# GBA.net
KiCad netlist of a schematic drawn in Altium Designer
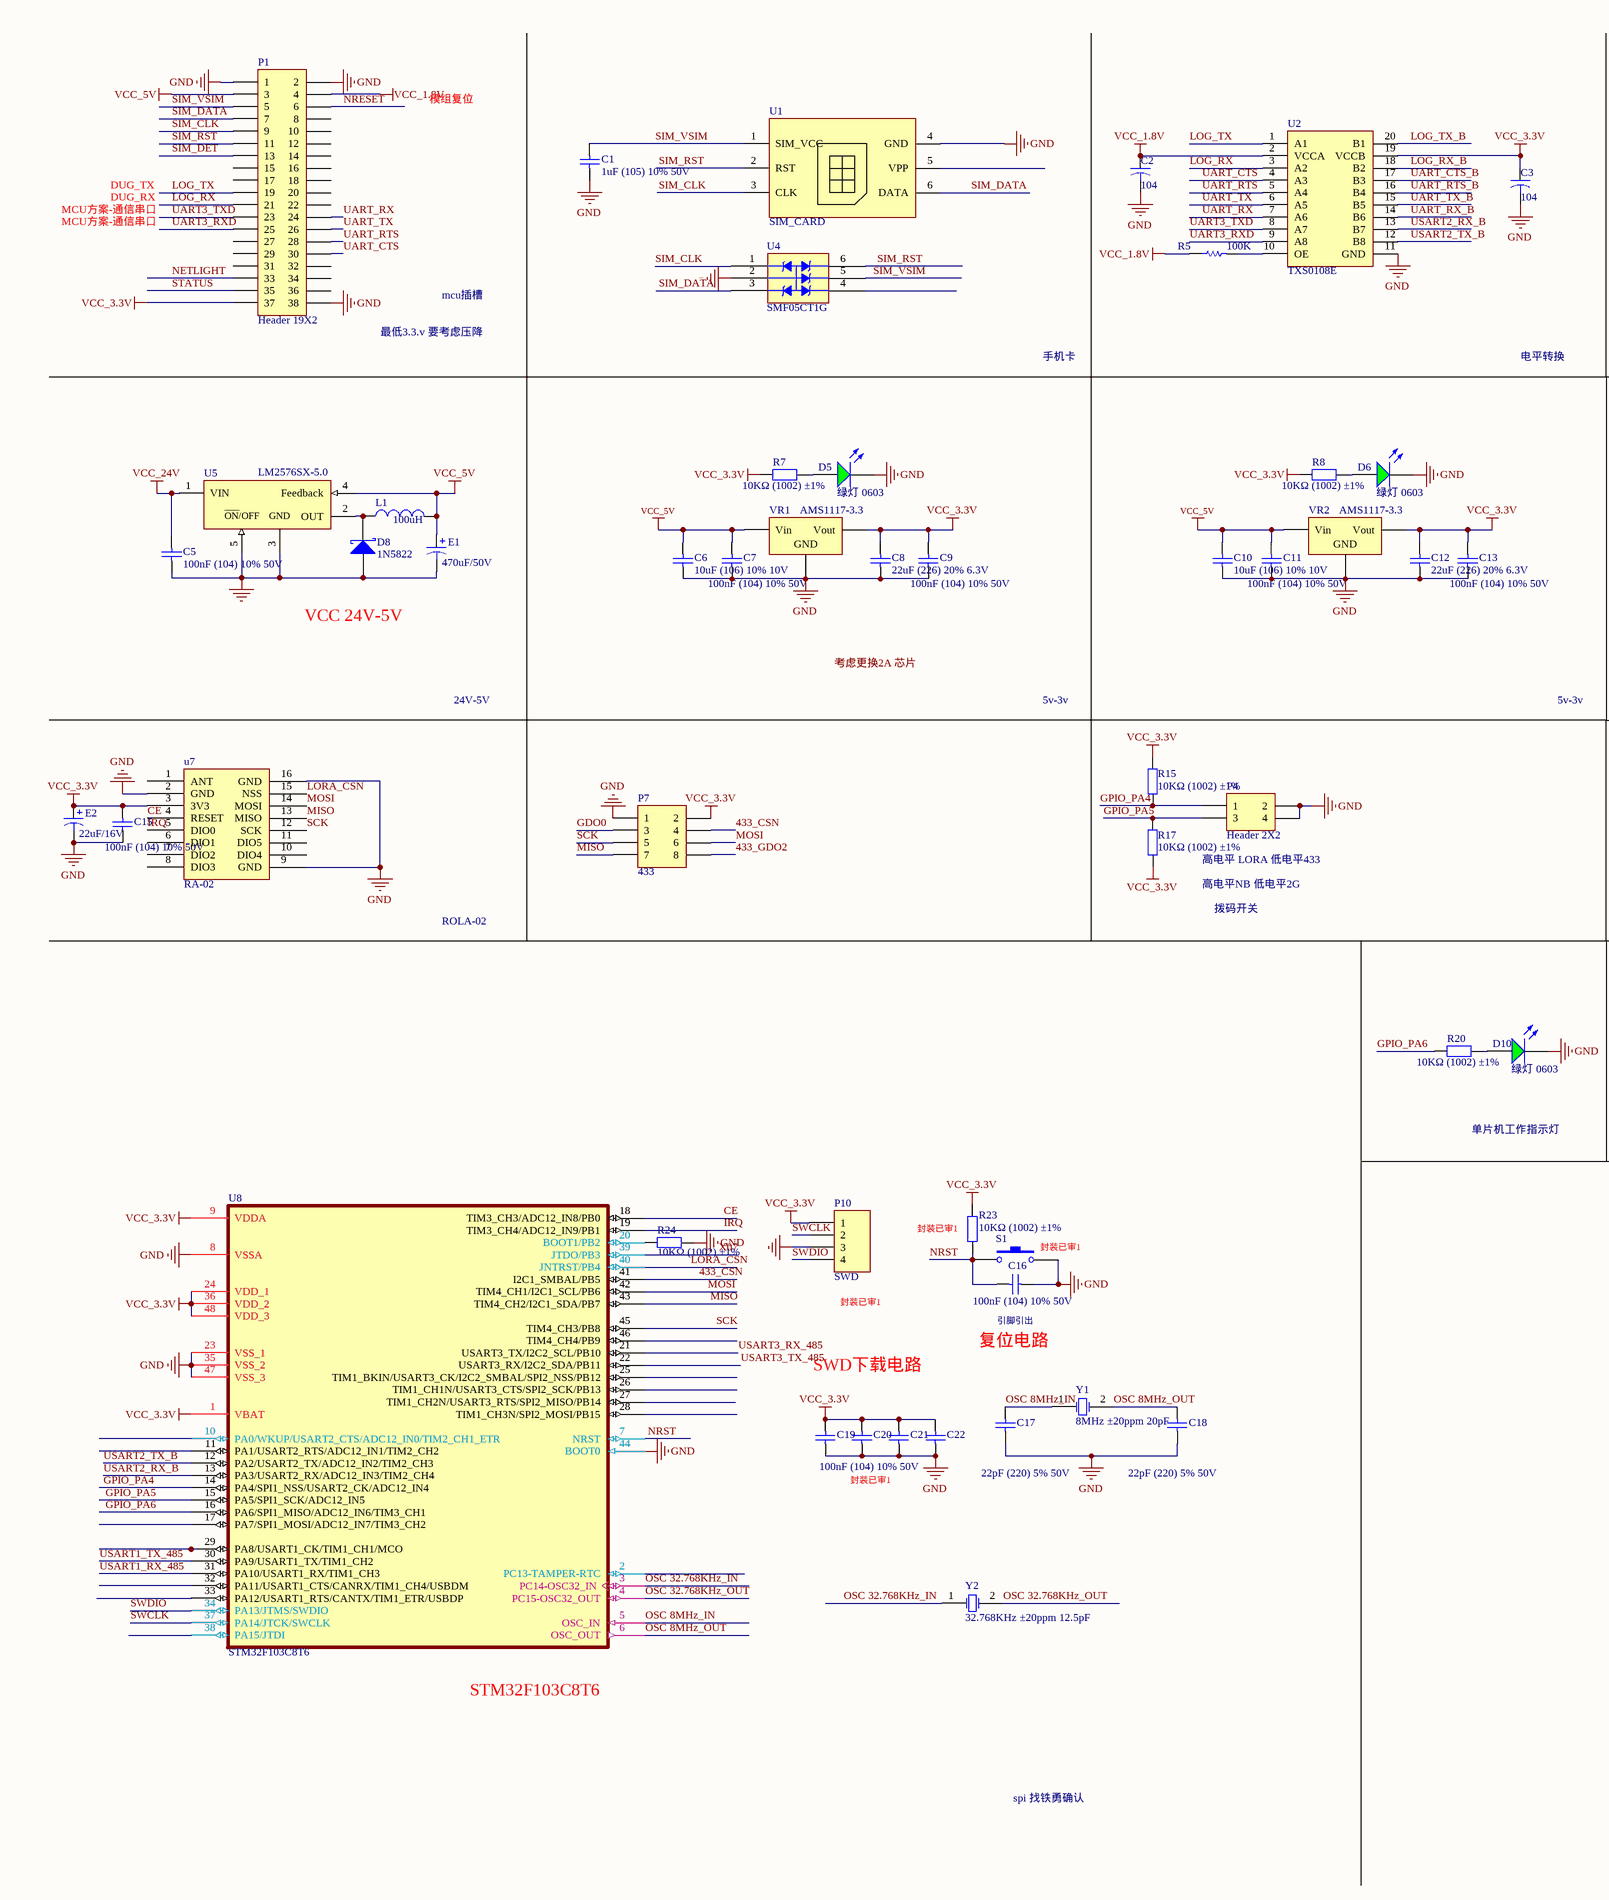
[diagram p0: GBA.SchDoc, left]
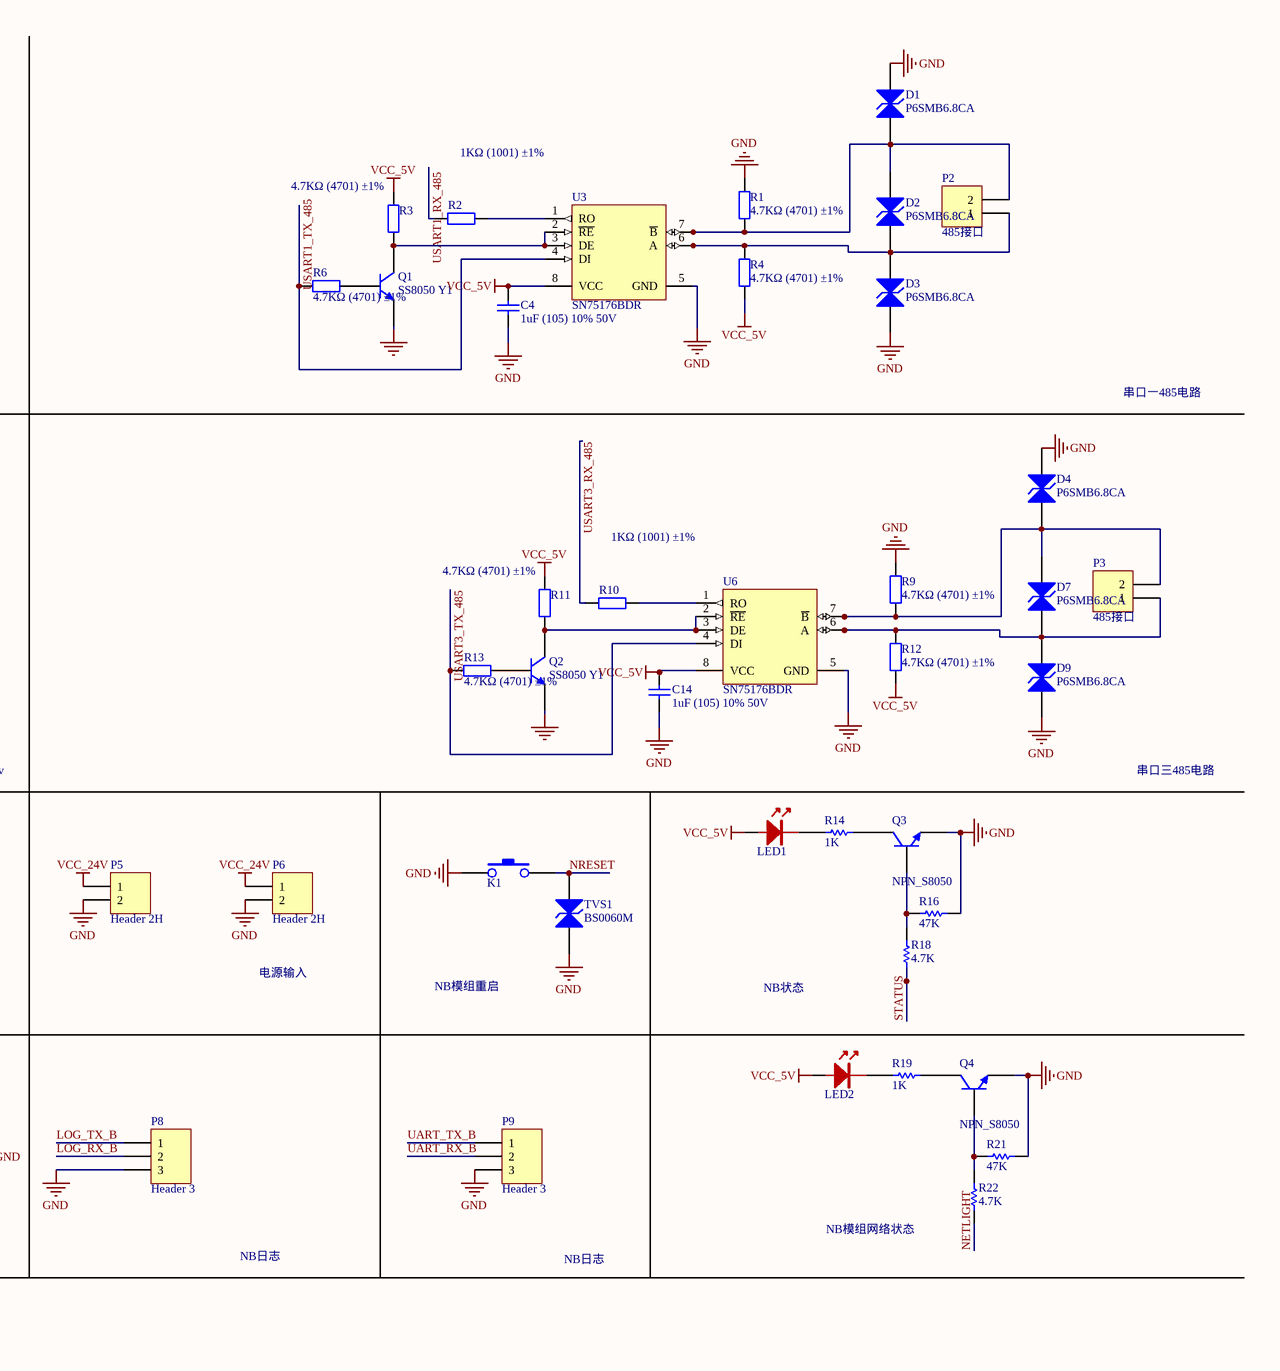
[diagram p1: GBA.SchDoc, right]

(export (version "E")
  (design (tool "Eeschema 10.0.6"))
  (components
    (comp (ref "C1")
      (value "1uF (105) 10% 50V")
      (footprint "0603_C")
      (description "贴片电容")
      (libsource (lib "Miscellaneous Devices LC (1)") (part "0603 1uF (105) 10% 50V"))
    )
    (comp (ref "C2") (value "104") (footprint "0603_s") (libsource (lib "WS_protel_lib") (part "Cap2")))
    (comp (ref "C3") (value "104") (footprint "0603_s") (libsource (lib "WS_protel_lib") (part "Cap2")))
    (comp (ref "C4")
      (value "1uF (105) 10% 50V")
      (footprint "0603_C")
      (description "贴片电容")
      (libsource (lib "Miscellaneous Devices LC (1)") (part "0603 1uF (105) 10% 50V"))
    )
    (comp (ref "C5")
      (value "100nF (104) 10% 50V")
      (footprint "0603_C")
      (description "贴片电容")
      (libsource (lib "Miscellaneous Devices LC") (part "0603 100nF (104) 10% 50V"))
    )
    (comp (ref "C6")
      (value "10uF (106) 10% 10V")
      (footprint "0603_C")
      (description "贴片电容")
      (libsource (lib "Miscellaneous Devices LC") (part "0603 10uF (106) 10% 10V"))
    )
    (comp (ref "C7")
      (value "100nF (104) 10% 50V")
      (footprint "CAPC_0603_2")
      (description "贴片电容")
      (libsource (lib "Cap") (part "0603 100nF (104) 10% 50V"))
    )
    (comp (ref "C8")
      (value "22uF (226) 20% 6.3V")
      (footprint "0603_C")
      (description "贴片电容")
      (libsource (lib "Miscellaneous Devices LC") (part "0603 22uF (226) 20% 6.3V"))
    )
    (comp (ref "C9")
      (value "100nF (104) 10% 50V")
      (footprint "CAPC_0603_2")
      (description "贴片电容")
      (libsource (lib "Cap") (part "0603 100nF (104) 10% 50V"))
    )
    (comp (ref "C10")
      (value "10uF (106) 10% 10V")
      (footprint "0603_C")
      (description "贴片电容")
      (libsource (lib "Miscellaneous Devices LC") (part "0603 10uF (106) 10% 10V"))
    )
    (comp (ref "C11")
      (value "100nF (104) 10% 50V")
      (footprint "CAPC_0603_2")
      (description "贴片电容")
      (libsource (lib "Cap") (part "0603 100nF (104) 10% 50V"))
    )
    (comp (ref "C12")
      (value "22uF (226) 20% 6.3V")
      (footprint "0603_C")
      (description "贴片电容")
      (libsource (lib "Miscellaneous Devices LC") (part "0603 22uF (226) 20% 6.3V"))
    )
    (comp (ref "C13")
      (value "100nF (104) 10% 50V")
      (footprint "CAPC_0603_2")
      (description "贴片电容")
      (libsource (lib "Cap") (part "0603 100nF (104) 10% 50V"))
    )
    (comp (ref "C14")
      (value "1uF (105) 10% 50V")
      (footprint "0603_C")
      (description "贴片电容")
      (libsource (lib "Miscellaneous Devices LC (1)") (part "0603 1uF (105) 10% 50V"))
    )
    (comp (ref "C15")
      (value "100nF (104) 10% 50V")
      (footprint "CAPC_0603_2")
      (description "贴片电容")
      (libsource (lib "Cap") (part "0603 100nF (104) 10% 50V"))
    )
    (comp (ref "C16")
      (value "100nF (104) 10% 50V")
      (footprint "CAPC_0603_2")
      (description "贴片电容")
      (libsource (lib "Cap") (part "0603 100nF (104) 10% 50V"))
    )
    (comp (ref "C17")
      (value "22pF (220) 5% 50V")
      (footprint "0603_C")
      (description "贴片电容")
      (libsource (lib "Miscellaneous Devices LC") (part "0603 22pF (220) 5% 50V"))
    )
    (comp (ref "C18")
      (value "22pF (220) 5% 50V")
      (footprint "0603_C")
      (description "贴片电容")
      (libsource (lib "Miscellaneous Devices LC") (part "0603 22pF (220) 5% 50V"))
    )
    (comp (ref "C19")
      (value "100nF (104) 10% 50V")
      (footprint "CAPC_0603_2")
      (description "贴片电容")
      (libsource (lib "Cap") (part "0603 100nF (104) 10% 50V"))
    )
    (comp (ref "C20")
      (value "100nF (104) 10% 50V")
      (footprint "CAPC_0603_2")
      (description "贴片电容")
      (libsource (lib "Cap") (part "0603 100nF (104) 10% 50V"))
    )
    (comp (ref "C21")
      (value "100nF (104) 10% 50V")
      (footprint "CAPC_0603_2")
      (description "贴片电容")
      (libsource (lib "Cap") (part "0603 100nF (104) 10% 50V"))
    )
    (comp (ref "C22")
      (value "100nF (104) 10% 50V")
      (footprint "CAPC_0603_2")
      (description "贴片电容")
      (libsource (lib "Cap") (part "0603 100nF (104) 10% 50V"))
    )
    (comp (ref "D1")
      (value "P6SMB6.8CA")
      (footprint "SMB(DO-214AA)_S1")
      (description "TVS")
      (libsource (lib "Miscellaneous Devices LC (1)") (part "SMB/DO-214AA P6SMB6.8CA"))
    )
    (comp (ref "D2")
      (value "P6SMB6.8CA")
      (footprint "SMB(DO-214AA)_S1")
      (description "TVS")
      (libsource (lib "Miscellaneous Devices LC (1)") (part "SMB/DO-214AA P6SMB6.8CA"))
    )
    (comp (ref "D3")
      (value "P6SMB6.8CA")
      (footprint "SMB(DO-214AA)_S1")
      (description "TVS")
      (libsource (lib "Miscellaneous Devices LC (1)") (part "SMB/DO-214AA P6SMB6.8CA"))
    )
    (comp (ref "D4")
      (value "P6SMB6.8CA")
      (footprint "SMB(DO-214AA)_S1")
      (description "TVS")
      (libsource (lib "Miscellaneous Devices LC (1)") (part "SMB/DO-214AA P6SMB6.8CA"))
    )
    (comp (ref "D5")
      (value "绿灯 0603")
      (footprint "0603_LED_S1")
      (description "发光二极管")
      (libsource (lib "LED") (part "0603 绿灯"))
    )
    (comp (ref "D6")
      (value "绿灯 0603")
      (footprint "0603_LED_S1")
      (description "发光二极管")
      (libsource (lib "LED") (part "0603 绿灯"))
    )
    (comp (ref "D7")
      (value "P6SMB6.8CA")
      (footprint "SMB(DO-214AA)_S1")
      (description "TVS")
      (libsource (lib "Miscellaneous Devices LC (1)") (part "SMB/DO-214AA P6SMB6.8CA"))
    )
    (comp (ref "D8")
      (value "1N5822")
      (footprint "DO214_SMA")
      (description "整流二极管")
      (libsource (lib "二极管") (part "SMA(DO-214AC) 1N5822"))
    )
    (comp (ref "D9")
      (value "P6SMB6.8CA")
      (footprint "SMB(DO-214AA)_S1")
      (description "TVS")
      (libsource (lib "Miscellaneous Devices LC (1)") (part "SMB/DO-214AA P6SMB6.8CA"))
    )
    (comp (ref "D10")
      (value "绿灯 0603")
      (footprint "0603_LED_S1")
      (description "发光二极管")
      (libsource (lib "LED") (part "0603 绿灯"))
    )
    (comp (ref "E1")
      (value "470uF/50V")
      (footprint "CAP_PR_5.0_13")
      (description "Polarized Capacitor (Radial)")
      (fields (field (name "Comment") "Cap Pol1") (field (name "PUBLISHER") "Altium Limited"))
      (libsource (lib "Miscellaneous Devices") (part "Cap Pol1"))
    )
    (comp (ref "E2")
      (value "22uF/16V")
      (footprint "CAP_PR_5.0_13")
      (description "Polarized Capacitor (Radial)")
      (fields (field (name "Comment") "Cap Pol1") (field (name "PUBLISHER") "Altium Limited"))
      (libsource (lib "Miscellaneous Devices") (part "Cap Pol1"))
    )
    (comp (ref "K1") (value "KEY") (footprint "KEY_4_s") (libsource (lib "WS_protel_lib") (part "KEY4")))
    (comp (ref "L1")
      (value "100uH")
      (footprint "Inductor_CDRH127R")
      (description "Inductor")
      (fields (field (name "PUBLISHER") "Altium Limited"))
      (libsource (lib "Miscellaneous Devices") (part "Inductor"))
    )
    (comp (ref "LED1")
      (value "LED_0805")
      (footprint "0805_LED")
      (libsource (lib "WS_protel_lib") (part "LED_0805"))
    )
    (comp (ref "LED2")
      (value "LED_0805")
      (footprint "0805_LED")
      (libsource (lib "WS_protel_lib") (part "LED_0805"))
    )
    (comp (ref "P1")
      (value "Header 19X2")
      (footprint "GOKIT4_DIP")
      (description "Header, 19-Pin, Dual row")
      (fields (field (name "PUBLISHER") "Altium Limited"))
      (libsource (lib "WS_protel_lib") (part "Header 19X2"))
    )
    (comp (ref "P2")
      (value "485接口")
      (footprint "2EDGK-2P")
      (description "Header, 2-Pin")
      (fields (field (name "PUBLISHER") "Altium Limited"))
      (libsource (lib "Miscellaneous Connectors") (part "Header 2"))
    )
    (comp (ref "P3")
      (value "485接口")
      (footprint "2EDGK-2P")
      (description "Header, 2-Pin")
      (fields (field (name "PUBLISHER") "Altium Limited"))
      (libsource (lib "Miscellaneous Connectors") (part "Header 2"))
    )
    (comp (ref "P4")
      (value "Header 2X2")
      (footprint "HDR2X2")
      (description "Header, 2-Pin, Dual row")
      (fields (field (name "PUBLISHER") "Altium Limited"))
      (libsource (lib "Miscellaneous Connectors") (part "Header 2X2"))
    )
    (comp (ref "P5")
      (value "Header 2H")
      (footprint "HDR1X2H")
      (description "Header, 2-Pin, Right Angle")
      (fields (field (name "PUBLISHER") "Altium Limited"))
      (libsource (lib "Miscellaneous Connectors") (part "Header 2H"))
    )
    (comp (ref "P6")
      (value "Header 2H")
      (footprint "HDR1X2H")
      (description "Header, 2-Pin, Right Angle")
      (fields (field (name "PUBLISHER") "Altium Limited"))
      (libsource (lib "Miscellaneous Connectors") (part "Header 2H"))
    )
    (comp (ref "P7")
      (value "433")
      (footprint "HDR2X4")
      (description "Header, 4-Pin, Dual row")
      (fields (field (name "PUBLISHER") "Altium Limited"))
      (libsource (lib "Miscellaneous Connectors") (part "Header 4X2"))
    )
    (comp (ref "P8")
      (value "Header 3")
      (footprint "HDR1X3")
      (description "Header, 3-Pin")
      (fields (field (name "PUBLISHER") "Altium Limited"))
      (libsource (lib "Miscellaneous Connectors") (part "Header 3"))
    )
    (comp (ref "P9")
      (value "Header 3")
      (footprint "HDR1X3")
      (description "Header, 3-Pin")
      (fields (field (name "PUBLISHER") "Altium Limited"))
      (libsource (lib "Miscellaneous Connectors") (part "Header 3"))
    )
    (comp (ref "P10")
      (value "Header 2.54X4")
      (footprint "Header 2.54X4")
      (description "Header, 4-Pin")
      (fields (field (name "SWD") "SWD") (field (name "PUBLISHER") "Altium Limited"))
      (libsource (lib "*") (part "Header 4"))
    )
    (comp (ref "Q1")
      (value "SS8050 Y1")
      (footprint "SOT-23(SOT-23-3)")
      (description "三极管")
      (libsource (lib "Miscellaneous Devices LC (1)") (part "SOT-23 SS8050 Y1"))
    )
    (comp (ref "Q2")
      (value "SS8050 Y1")
      (footprint "SOT-23(SOT-23-3)")
      (description "三极管")
      (libsource (lib "Miscellaneous Devices LC (1)") (part "SOT-23 SS8050 Y1"))
    )
    (comp (ref "Q3")
      (value "NPN_S8050")
      (footprint "SOT-23")
      (libsource (lib "WS_protel_lib") (part "NPN_SOT23"))
    )
    (comp (ref "Q4")
      (value "NPN_S8050")
      (footprint "SOT-23")
      (libsource (lib "WS_protel_lib") (part "NPN_SOT23"))
    )
    (comp (ref "R1")
      (value "4.7KΩ (4701) ±1%")
      (footprint "0603_R")
      (description "贴片电阻")
      (libsource (lib "Miscellaneous Devices LC (1)") (part "0603 4.7KΩ (4701) 1%"))
    )
    (comp (ref "R2")
      (value "1KΩ (1001) ±1%")
      (footprint "0603_R")
      (description "贴片电阻")
      (libsource (lib "Miscellaneous Devices LC (1)") (part "0603 1KΩ (1001) 1%"))
    )
    (comp (ref "R3")
      (value "4.7KΩ (4701) ±1%")
      (footprint "0603_R")
      (description "贴片电阻")
      (libsource (lib "Miscellaneous Devices LC (1)") (part "0603 4.7KΩ (4701) 1%"))
    )
    (comp (ref "R4")
      (value "4.7KΩ (4701) ±1%")
      (footprint "0603_R")
      (description "贴片电阻")
      (libsource (lib "Miscellaneous Devices LC (1)") (part "0603 4.7KΩ (4701) 1%"))
    )
    (comp (ref "R5")
      (value "100K")
      (footprint "0603_s")
      (description "Resistor")
      (libsource (lib "WS_protel_lib") (part "Res1"))
    )
    (comp (ref "R6")
      (value "4.7KΩ (4701) ±1%")
      (footprint "0603_R")
      (description "贴片电阻")
      (libsource (lib "") (part "0603 4.7KΩ (4701) 1%_1"))
    )
    (comp (ref "R7")
      (value "10KΩ (1002) ±1%")
      (footprint "RESC_0603_2")
      (description "贴片电阻")
      (libsource (lib "") (part "0603 10KΩ (1002) 1%_1"))
    )
    (comp (ref "R8")
      (value "10KΩ (1002) ±1%")
      (footprint "RESC_0603_2")
      (description "贴片电阻")
      (libsource (lib "") (part "0603 10KΩ (1002) 1%_1"))
    )
    (comp (ref "R9")
      (value "4.7KΩ (4701) ±1%")
      (footprint "0603_R")
      (description "贴片电阻")
      (libsource (lib "Miscellaneous Devices LC (1)") (part "0603 4.7KΩ (4701) 1%"))
    )
    (comp (ref "R10")
      (value "1KΩ (1001) ±1%")
      (footprint "0603_R")
      (description "贴片电阻")
      (libsource (lib "Miscellaneous Devices LC (1)") (part "0603 1KΩ (1001) 1%"))
    )
    (comp (ref "R11")
      (value "4.7KΩ (4701) ±1%")
      (footprint "0603_R")
      (description "贴片电阻")
      (libsource (lib "Miscellaneous Devices LC (1)") (part "0603 4.7KΩ (4701) 1%"))
    )
    (comp (ref "R12")
      (value "4.7KΩ (4701) ±1%")
      (footprint "0603_R")
      (description "贴片电阻")
      (libsource (lib "Miscellaneous Devices LC (1)") (part "0603 4.7KΩ (4701) 1%"))
    )
    (comp (ref "R13")
      (value "4.7KΩ (4701) ±1%")
      (footprint "0603_R")
      (description "贴片电阻")
      (libsource (lib "") (part "0603 4.7KΩ (4701) 1%_1"))
    )
    (comp (ref "R14")
      (value "1K")
      (footprint "0603_s")
      (description "Resistor")
      (libsource (lib "WS_protel_lib") (part "Res1"))
    )
    (comp (ref "R15")
      (value "10KΩ (1002) ±1%")
      (footprint "RESC_0603_2")
      (description "贴片电阻")
      (libsource (lib "RES") (part "0603 10KΩ (1002) 1%"))
    )
    (comp (ref "R16")
      (value "47K")
      (footprint "0603_s")
      (description "Resistor")
      (libsource (lib "WS_protel_lib") (part "Res1"))
    )
    (comp (ref "R17")
      (value "10KΩ (1002) ±1%")
      (footprint "RESC_0603_2")
      (description "贴片电阻")
      (libsource (lib "RES") (part "0603 10KΩ (1002) 1%"))
    )
    (comp (ref "R18")
      (value "4.7K")
      (footprint "0603_s")
      (description "Resistor")
      (libsource (lib "WS_protel_lib") (part "Res1"))
    )
    (comp (ref "R19")
      (value "1K")
      (footprint "0603_s")
      (description "Resistor")
      (libsource (lib "WS_protel_lib") (part "Res1"))
    )
    (comp (ref "R20")
      (value "10KΩ (1002) ±1%")
      (footprint "RESC_0603_2")
      (description "贴片电阻")
      (libsource (lib "") (part "0603 10KΩ (1002) 1%_1"))
    )
    (comp (ref "R21")
      (value "47K")
      (footprint "0603_s")
      (description "Resistor")
      (libsource (lib "WS_protel_lib") (part "Res1"))
    )
    (comp (ref "R22")
      (value "4.7K")
      (footprint "0603_s")
      (description "Resistor")
      (libsource (lib "WS_protel_lib") (part "Res1"))
    )
    (comp (ref "R23")
      (value "10KΩ (1002) ±1%")
      (footprint "RESC_0603_2")
      (description "贴片电阻")
      (libsource (lib "RES") (part "0603 10KΩ (1002) 1%"))
    )
    (comp (ref "R24")
      (value "10KΩ (1002) ±1%")
      (footprint "RESC_0603_2")
      (description "贴片电阻")
      (libsource (lib "") (part "0603 10KΩ (1002) 1%_1"))
    )
    (comp (ref "S1")
      (value "SW-PB")
      (footprint "SW_PB_3X6")
      (description "微动开关")
      (fields (field (name "PUBLISHER") "Altium Limited"))
      (libsource (lib "自己的库") (part "SW-PB_1"))
    )
    (comp (ref "TVS1")
      (value "BS0060M")
      (footprint "0603_s")
      (libsource (lib "WS_protel_lib") (part "BS0060M"))
    )
    (comp (ref "U1")
      (value "SIM_CARD")
      (footprint "SIM_MICRO_6P_F")
      (libsource (lib "pcb 封装2") (part "SIM_CARD"))
    )
    (comp (ref "U2")
      (value "TXS0108E")
      (footprint "TXS0108E")
      (libsource (lib "WS_protel_lib") (part "TXS0108E"))
    )
    (comp (ref "U3")
      (value "SN75176BDR")
      (footprint "SOIC-8_150mil")
      (description "RS-485/RS-422")
      (libsource (lib "Miscellaneous Devices LC (1)") (part "SN75176BDR_[C7063]"))
    )
    (comp (ref "U4")
      (value "SMF05CT1G")
      (footprint "SC-70-6(SOT-363)")
      (description "TVS")
      (libsource (lib "Miscellaneous Devices LC (1)") (part "SMF05CT1G_[C15879]"))
    )
    (comp (ref "U5")
      (value "LM2576SX-5.0")
      (footprint "TO-263-5")
      (description "DC-DC芯片")
      (libsource (lib "IC芯片") (part "LM2576SX-5.0_[C34465]"))
    )
    (comp (ref "U6")
      (value "SN75176BDR")
      (footprint "SOIC-8_150mil")
      (description "RS-485/RS-422")
      (libsource (lib "Miscellaneous Devices LC (1)") (part "SN75176BDR_[C7063]"))
    )
    (comp (ref "u7") (value "RA-02") (libsource (lib "特殊封装") (part "RA")))
    (comp (ref "U8")
      (value "STM32F103C8T6")
      (footprint "LQFP-48_7x7x05P")
      (description "ARM")
      (libsource (lib "MCU") (part "STM32F103C8T6"))
    )
    (comp (ref "VR1")
      (value "AMS1117-3.3")
      (footprint "SOT-223")
      (description "低压差线性稳压(LDO)")
      (libsource (lib "LDO") (part "SOT-223 AMS1117-3.3"))
    )
    (comp (ref "VR2")
      (value "AMS1117-3.3")
      (footprint "SOT-223")
      (description "低压差线性稳压(LDO)")
      (libsource (lib "LDO") (part "SOT-223 AMS1117-3.3"))
    )
    (comp (ref "Y1")
      (value "8MHz ±20ppm 20pF")
      (footprint "SMD-5032_2P")
      (description "贴片晶振")
      (libsource (lib "CrystalOscillator") (part "SMD-5032_2P 8MHz 20ppm 20pF"))
    )
    (comp (ref "Y2")
      (value "32.768KHz ±20ppm 12.5pF")
      (footprint "SMD-3215_2P FC - 135")
      (description "贴片晶振")
      (libsource (lib "CrystalOscillator") (part "SMD-3215_2P 32.768KHz 20ppm 12.5pF"))
    )
  )
  (nets
    (net (code "1") (name "/433_CSN") (class "Default")
      (node (ref "P7") (pin "4") (pinfunction "4_4") (pintype "passive"))
      (node (ref "U8") (pin "41") (pinfunction "I2C1_SMBAL/PB5_41") (pintype "bidirectional"))
    )
    (net (code "2") (name "/433_GDO2") (class "Default")
      (node (ref "P7") (pin "8") (pinfunction "8_8") (pintype "passive"))
    )
    (net (code "3") (name "/CE") (class "Default")
      (node (ref "U8") (pin "18") (pinfunction "TIM3_CH3/ADC12_IN8/PB0_18") (pintype "bidirectional"))
      (node (ref "u7") (pin "4") (pinfunction "RESET_4") (pintype "passive"))
    )
    (net (code "4") (name "/GDO0") (class "Default")
      (node (ref "P7") (pin "3") (pinfunction "3_3") (pintype "passive"))
    )
    (net (code "5") (name "/GPIO_PA4") (class "Default")
      (node (ref "P4") (pin "1") (pinfunction "1_1") (pintype "passive"))
      (node (ref "R15") (pin "1") (pinfunction "1_1") (pintype "passive"))
      (node (ref "U8") (pin "14") (pinfunction "PA4/SPI1_NSS/USART2_CK/ADC12_IN4_14") (pintype "bidirectional"))
    )
    (net (code "6") (name "/GPIO_PA5") (class "Default")
      (node (ref "P4") (pin "3") (pinfunction "3_3") (pintype "passive"))
      (node (ref "R17") (pin "2") (pinfunction "2_2") (pintype "passive"))
      (node (ref "U8") (pin "15") (pinfunction "PA5/SPI1_SCK/ADC12_IN5_15") (pintype "bidirectional"))
    )
    (net (code "7") (name "/GPIO_PA6") (class "Default")
      (node (ref "R20") (pin "1") (pinfunction "1_1") (pintype "passive"))
      (node (ref "U8") (pin "16") (pinfunction "PA6/SPI1_MISO/ADC12_IN6/TIM3_CH1_16") (pintype "bidirectional"))
    )
    (net (code "8") (name "/IRQ") (class "Default")
      (node (ref "U8") (pin "19") (pinfunction "TIM3_CH4/ADC12_IN9/PB1_19") (pintype "bidirectional"))
      (node (ref "u7") (pin "5") (pinfunction "DIO0_5") (pintype "passive"))
    )
    (net (code "9") (name "/LOG_RX") (class "Default")
      (node (ref "P1") (pin "21") (pinfunction "21_21") (pintype "passive"))
      (node (ref "U2") (pin "3") (pinfunction "A2_3") (pintype "passive"))
    )
    (net (code "10") (name "/LOG_RX_B") (class "Default")
      (node (ref "P8") (pin "2") (pinfunction "2_2") (pintype "passive"))
      (node (ref "U2") (pin "18") (pinfunction "B2_18") (pintype "passive"))
    )
    (net (code "11") (name "/LOG_TX") (class "Default")
      (node (ref "P1") (pin "19") (pinfunction "19_19") (pintype "passive"))
      (node (ref "U2") (pin "1") (pinfunction "A1_1") (pintype "passive"))
    )
    (net (code "12") (name "/LOG_TX_B") (class "Default")
      (node (ref "P8") (pin "1") (pinfunction "1_1") (pintype "passive"))
      (node (ref "U2") (pin "20") (pinfunction "B1_20") (pintype "passive"))
    )
    (net (code "13") (name "/LORA_CSN") (class "Default")
      (node (ref "U8") (pin "40") (pinfunction "JNTRST/PB4_40") (pintype "bidirectional"))
      (node (ref "u7") (pin "15") (pinfunction "NSS_15") (pintype "passive"))
    )
    (net (code "14") (name "/MISO") (class "Default")
      (node (ref "P7") (pin "7") (pinfunction "7_7") (pintype "passive"))
      (node (ref "U8") (pin "43") (pinfunction "TIM4_CH2/I2C1_SDA/PB7_43") (pintype "bidirectional"))
      (node (ref "u7") (pin "13") (pinfunction "MISO_13") (pintype "passive"))
    )
    (net (code "15") (name "/MOSI") (class "Default")
      (node (ref "P7") (pin "6") (pinfunction "6_6") (pintype "passive"))
      (node (ref "U8") (pin "42") (pinfunction "TIM4_CH1/I2C1_SCL/PB6_42") (pintype "bidirectional"))
      (node (ref "u7") (pin "14") (pinfunction "MOSI_14") (pintype "passive"))
    )
    (net (code "16") (name "/NETLIGHT") (class "Default")
      (node (ref "P1") (pin "33") (pinfunction "33_33") (pintype "passive"))
      (node (ref "R22") (pin "2") (pinfunction "2_2") (pintype "passive"))
    )
    (net (code "17") (name "/NRESET") (class "Default")
      (node (ref "K1") (pin "2") (pinfunction "2_2") (pintype "passive"))
      (node (ref "P1") (pin "6") (pinfunction "6_6") (pintype "passive"))
      (node (ref "TVS1") (pin "2") (pinfunction "K_2") (pintype "passive"))
    )
    (net (code "18") (name "/NRST") (class "Default")
      (node (ref "C16") (pin "2") (pinfunction "2_2") (pintype "passive"))
      (node (ref "R23") (pin "1") (pinfunction "1_1") (pintype "passive"))
      (node (ref "S1") (pin "1") (pinfunction "1_1") (pintype "passive"))
      (node (ref "U8") (pin "7") (pinfunction "NRST_7") (pintype "bidirectional"))
    )
    (net (code "19") (name "/OSC 8MHz_IN") (class "Default")
      (node (ref "C17") (pin "2") (pinfunction "2_2") (pintype "passive"))
      (node (ref "U8") (pin "5") (pinfunction "OSC_IN_5") (pintype "input"))
      (node (ref "Y1") (pin "1") (pinfunction "OSC1_1") (pintype "passive"))
    )
    (net (code "20") (name "/OSC 8MHz_OUT") (class "Default")
      (node (ref "C18") (pin "2") (pinfunction "2_2") (pintype "passive"))
      (node (ref "U8") (pin "6") (pinfunction "OSC_OUT_6") (pintype "output"))
      (node (ref "Y1") (pin "2") (pinfunction "OSC2_2") (pintype "passive"))
    )
    (net (code "21") (name "/OSC 32.768KHz_IN") (class "Default")
      (node (ref "U8") (pin "3") (pinfunction "PC14-OSC32_IN_3") (pintype "bidirectional"))
      (node (ref "Y2") (pin "1") (pinfunction "OSC1_1") (pintype "passive"))
    )
    (net (code "22") (name "/OSC 32.768KHz_OUT") (class "Default")
      (node (ref "U8") (pin "4") (pinfunction "PC15-OSC32_OUT_4") (pintype "bidirectional"))
      (node (ref "Y2") (pin "2") (pinfunction "OSC2_2") (pintype "passive"))
    )
    (net (code "23") (name "/SCK") (class "Default")
      (node (ref "P7") (pin "5") (pinfunction "5_5") (pintype "passive"))
      (node (ref "U8") (pin "45") (pinfunction "TIM4_CH3/PB8_45") (pintype "bidirectional"))
      (node (ref "u7") (pin "12") (pinfunction "SCK_12") (pintype "passive"))
    )
    (net (code "24") (name "/SIM_CLK") (class "Default")
      (node (ref "P1") (pin "9") (pinfunction "9_9") (pintype "passive"))
      (node (ref "U1") (pin "3") (pinfunction "CLK_3") (pintype "passive"))
      (node (ref "U4") (pin "1") (pinfunction "1_1") (pintype "passive"))
    )
    (net (code "25") (name "/SIM_DATA") (class "Default")
      (node (ref "P1") (pin "7") (pinfunction "7_7") (pintype "passive"))
      (node (ref "U1") (pin "6") (pinfunction "DATA_6") (pintype "passive"))
      (node (ref "U4") (pin "3") (pinfunction "3_3") (pintype "passive"))
    )
    (net (code "26") (name "/SIM_DET") (class "Default")
      (node (ref "P1") (pin "13") (pinfunction "13_13") (pintype "passive"))
    )
    (net (code "27") (name "/SIM_RST") (class "Default")
      (node (ref "P1") (pin "11") (pinfunction "11_11") (pintype "passive"))
      (node (ref "U1") (pin "2") (pinfunction "RST_2") (pintype "passive"))
      (node (ref "U4") (pin "6") (pinfunction "6_6") (pintype "passive"))
    )
    (net (code "28") (name "/SIM_VSIM") (class "Default")
      (node (ref "C1") (pin "2") (pinfunction "2_2") (pintype "passive"))
      (node (ref "P1") (pin "5") (pinfunction "5_5") (pintype "passive"))
      (node (ref "U1") (pin "1") (pinfunction "SIM_VCC_1") (pintype "passive"))
      (node (ref "U4") (pin "5") (pinfunction "5_5") (pintype "passive"))
    )
    (net (code "29") (name "/STATUS") (class "Default")
      (node (ref "P1") (pin "35") (pinfunction "35_35") (pintype "passive"))
      (node (ref "R18") (pin "2") (pinfunction "2_2") (pintype "passive"))
    )
    (net (code "30") (name "/SWCLK") (class "Default")
      (node (ref "P10") (pin "2") (pinfunction "2_2") (pintype "passive"))
      (node (ref "U8") (pin "37") (pinfunction "PA14/JTCK/SWCLK_37") (pintype "bidirectional"))
    )
    (net (code "31") (name "/SWDIO") (class "Default")
      (node (ref "P10") (pin "4") (pinfunction "4_4") (pintype "passive"))
      (node (ref "U8") (pin "34") (pinfunction "PA13/JTMS/SWDIO_34") (pintype "bidirectional"))
    )
    (net (code "32") (name "/UART3_RXD") (class "Default")
      (node (ref "P1") (pin "25") (pinfunction "25_25") (pintype "passive"))
      (node (ref "U2") (pin "9") (pinfunction "A8_9") (pintype "passive"))
    )
    (net (code "33") (name "/UART3_TXD") (class "Default")
      (node (ref "P1") (pin "23") (pinfunction "23_23") (pintype "passive"))
      (node (ref "U2") (pin "8") (pinfunction "A7_8") (pintype "passive"))
    )
    (net (code "34") (name "/UART_CTS") (class "Default")
      (node (ref "P1") (pin "30") (pinfunction "30_30") (pintype "passive"))
      (node (ref "U2") (pin "4") (pinfunction "A3_4") (pintype "passive"))
    )
    (net (code "35") (name "/UART_CTS_B") (class "Default")
      (node (ref "U2") (pin "17") (pinfunction "B3_17") (pintype "passive"))
    )
    (net (code "36") (name "/UART_RTS") (class "Default")
      (node (ref "P1") (pin "28") (pinfunction "28_28") (pintype "passive"))
      (node (ref "U2") (pin "5") (pinfunction "A4_5") (pintype "passive"))
    )
    (net (code "37") (name "/UART_RTS_B") (class "Default")
      (node (ref "U2") (pin "16") (pinfunction "B4_16") (pintype "passive"))
    )
    (net (code "38") (name "/UART_RX") (class "Default")
      (node (ref "P1") (pin "24") (pinfunction "24_24") (pintype "passive"))
      (node (ref "U2") (pin "7") (pinfunction "A6_7") (pintype "passive"))
    )
    (net (code "39") (name "/UART_RX_B") (class "Default")
      (node (ref "P9") (pin "2") (pinfunction "2_2") (pintype "passive"))
      (node (ref "U2") (pin "14") (pinfunction "B6_14") (pintype "passive"))
    )
    (net (code "40") (name "/UART_TX") (class "Default")
      (node (ref "P1") (pin "26") (pinfunction "26_26") (pintype "passive"))
      (node (ref "U2") (pin "6") (pinfunction "A5_6") (pintype "passive"))
    )
    (net (code "41") (name "/UART_TX_B") (class "Default")
      (node (ref "P9") (pin "1") (pinfunction "1_1") (pintype "passive"))
      (node (ref "U2") (pin "15") (pinfunction "B5_15") (pintype "passive"))
    )
    (net (code "42") (name "/USART1_RX_485") (class "Default")
      (node (ref "R2") (pin "1") (pinfunction "1_1") (pintype "passive"))
      (node (ref "U8") (pin "31") (pinfunction "PA10/USART1_RX/TIM1_CH3_31") (pintype "bidirectional"))
    )
    (net (code "43") (name "/USART1_TX_485") (class "Default")
      (node (ref "U8") (pin "30") (pinfunction "PA9/USART1_TX/TIM1_CH2_30") (pintype "bidirectional"))
    )
    (net (code "44") (name "/USART2_RX_B") (class "Default")
      (node (ref "U2") (pin "13") (pinfunction "B7_13") (pintype "passive"))
      (node (ref "U8") (pin "13") (pinfunction "PA3/USART2_RX/ADC12_IN3/TIM2_CH4_13") (pintype "bidirectional"))
    )
    (net (code "45") (name "/USART2_TX_B") (class "Default")
      (node (ref "U2") (pin "12") (pinfunction "B8_12") (pintype "passive"))
      (node (ref "U8") (pin "12") (pinfunction "PA2/USART2_TX/ADC12_IN2/TIM2_CH3_12") (pintype "bidirectional"))
    )
    (net (code "46") (name "/USART3_RX_485") (class "Default")
      (node (ref "R10") (pin "1") (pinfunction "1_1") (pintype "passive"))
      (node (ref "U8") (pin "21") (pinfunction "USART3_TX/I2C2_SCL/PB10_21") (pintype "bidirectional"))
    )
    (net (code "47") (name "/USART3_TX_485") (class "Default")
      (node (ref "R13") (pin "1") (pinfunction "1_1") (pintype "passive"))
      (node (ref "U6") (pin "4") (pinfunction "DI_4") (pintype "input"))
      (node (ref "U8") (pin "22") (pinfunction "USART3_RX/I2C2_SDA/PB11_22") (pintype "bidirectional"))
    )
    (net (code "48") (name "/X07") (class "Default")
      (node (ref "U8") (pin "39") (pinfunction "JTDO/PB3_39") (pintype "bidirectional"))
    )
    (net (code "50") (name "GND") (class "Default")
      (node (ref "C1") (pin "1") (pinfunction "1_1") (pintype "passive"))
      (node (ref "C10") (pin "1") (pinfunction "1_1") (pintype "passive"))
      (node (ref "C11") (pin "1") (pinfunction "1_1") (pintype "passive"))
      (node (ref "C12") (pin "1") (pinfunction "1_1") (pintype "passive"))
      (node (ref "C13") (pin "1") (pinfunction "1_1") (pintype "passive"))
      (node (ref "C14") (pin "1") (pinfunction "1_1") (pintype "passive"))
      (node (ref "C15") (pin "1") (pinfunction "1_1") (pintype "passive"))
      (node (ref "C16") (pin "1") (pinfunction "1_1") (pintype "passive"))
      (node (ref "C17") (pin "1") (pinfunction "1_1") (pintype "passive"))
      (node (ref "C18") (pin "1") (pinfunction "1_1") (pintype "passive"))
      (node (ref "C19") (pin "1") (pinfunction "1_1") (pintype "passive"))
      (node (ref "C2") (pin "2") (pinfunction "2_2") (pintype "passive"))
      (node (ref "C20") (pin "1") (pinfunction "1_1") (pintype "passive"))
      (node (ref "C21") (pin "1") (pinfunction "1_1") (pintype "passive"))
      (node (ref "C22") (pin "1") (pinfunction "1_1") (pintype "passive"))
      (node (ref "C3") (pin "2") (pinfunction "2_2") (pintype "passive"))
      (node (ref "C4") (pin "1") (pinfunction "1_1") (pintype "passive"))
      (node (ref "C5") (pin "1") (pinfunction "1_1") (pintype "passive"))
      (node (ref "C6") (pin "1") (pinfunction "1_1") (pintype "passive"))
      (node (ref "C7") (pin "1") (pinfunction "1_1") (pintype "passive"))
      (node (ref "C8") (pin "1") (pinfunction "1_1") (pintype "passive"))
      (node (ref "C9") (pin "1") (pinfunction "1_1") (pintype "passive"))
      (node (ref "D1") (pin "2") (pinfunction "K_2") (pintype "passive"))
      (node (ref "D10") (pin "K") (pinfunction "K_K") (pintype "passive"))
      (node (ref "D3") (pin "1") (pinfunction "A_1") (pintype "passive"))
      (node (ref "D4") (pin "2") (pinfunction "K_2") (pintype "passive"))
      (node (ref "D5") (pin "K") (pinfunction "K_K") (pintype "passive"))
      (node (ref "D6") (pin "K") (pinfunction "K_K") (pintype "passive"))
      (node (ref "D8") (pin "1") (pinfunction "A_1") (pintype "passive"))
      (node (ref "D9") (pin "1") (pinfunction "A_1") (pintype "passive"))
      (node (ref "E1") (pin "2") (pinfunction "2_2") (pintype "passive"))
      (node (ref "E2") (pin "2") (pinfunction "2_2") (pintype "passive"))
      (node (ref "K1") (pin "1") (pinfunction "1_1") (pintype "passive"))
      (node (ref "P1") (pin "1") (pinfunction "1_1") (pintype "passive"))
      (node (ref "P1") (pin "2") (pinfunction "2_2") (pintype "passive"))
      (node (ref "P1") (pin "38") (pinfunction "38_38") (pintype "passive"))
      (node (ref "P10") (pin "3") (pinfunction "3_3") (pintype "passive"))
      (node (ref "P4") (pin "2") (pinfunction "2_2") (pintype "passive"))
      (node (ref "P4") (pin "4") (pinfunction "4_4") (pintype "passive"))
      (node (ref "P5") (pin "2") (pinfunction "2_2") (pintype "passive"))
      (node (ref "P6") (pin "2") (pinfunction "2_2") (pintype "passive"))
      (node (ref "P7") (pin "1") (pinfunction "1_1") (pintype "passive"))
      (node (ref "P8") (pin "3") (pinfunction "3_3") (pintype "passive"))
      (node (ref "P9") (pin "3") (pinfunction "3_3") (pintype "passive"))
      (node (ref "Q1") (pin "2") (pinfunction "E_2") (pintype "passive"))
      (node (ref "Q2") (pin "2") (pinfunction "E_2") (pintype "passive"))
      (node (ref "Q3") (pin "2") (pinfunction "E_2") (pintype "passive"))
      (node (ref "Q4") (pin "2") (pinfunction "E_2") (pintype "passive"))
      (node (ref "R1") (pin "2") (pinfunction "2_2") (pintype "passive"))
      (node (ref "R16") (pin "2") (pinfunction "2_2") (pintype "passive"))
      (node (ref "R21") (pin "2") (pinfunction "2_2") (pintype "passive"))
      (node (ref "R24") (pin "2") (pinfunction "2_2") (pintype "passive"))
      (node (ref "R9") (pin "2") (pinfunction "2_2") (pintype "passive"))
      (node (ref "S1") (pin "2") (pinfunction "2_2") (pintype "passive"))
      (node (ref "TVS1") (pin "1") (pinfunction "A_1") (pintype "passive"))
      (node (ref "U1") (pin "4") (pinfunction "GND_4") (pintype "passive"))
      (node (ref "U2") (pin "11") (pinfunction "GND_11") (pintype "passive"))
      (node (ref "U3") (pin "5") (pinfunction "GND_5") (pintype "power_in"))
      (node (ref "U4") (pin "2") (pinfunction "2_2") (pintype "passive"))
      (node (ref "U5") (pin "3") (pinfunction "DGND_3") (pintype "passive"))
      (node (ref "U5") (pin "5") (pinfunction "ON/OFF_5") (pintype "input"))
      (node (ref "U6") (pin "5") (pinfunction "GND_5") (pintype "power_in"))
      (node (ref "U8") (pin "23") (pinfunction "VSS_1_23") (pintype "power_in"))
      (node (ref "U8") (pin "35") (pinfunction "VSS_2_35") (pintype "power_in"))
      (node (ref "U8") (pin "44") (pinfunction "BOOT0_44") (pintype "input"))
      (node (ref "U8") (pin "47") (pinfunction "VSS_3_47") (pintype "power_in"))
      (node (ref "U8") (pin "8") (pinfunction "VSSA_8") (pintype "power_in"))
      (node (ref "VR1") (pin "1") (pinfunction "GND_1") (pintype "passive"))
      (node (ref "VR2") (pin "1") (pinfunction "GND_1") (pintype "passive"))
      (node (ref "u7") (pin "16") (pinfunction "GND_16") (pintype "passive"))
      (node (ref "u7") (pin "2") (pinfunction "GND_2") (pintype "passive"))
      (node (ref "u7") (pin "9") (pinfunction "GND_9") (pintype "passive"))
    )
    (net (code "51") (name "Net-(D1-A)") (class "Default")
      (node (ref "D1") (pin "1") (pinfunction "A_1") (pintype "passive"))
      (node (ref "D2") (pin "2") (pinfunction "K_2") (pintype "passive"))
      (node (ref "P2") (pin "2") (pinfunction "2_2") (pintype "passive"))
      (node (ref "R1") (pin "1") (pinfunction "1_1") (pintype "passive"))
      (node (ref "U3") (pin "7") (pinfunction "~{B}_7") (pintype "bidirectional"))
    )
    (net (code "52") (name "Net-(D2-A)") (class "Default")
      (node (ref "D2") (pin "1") (pinfunction "A_1") (pintype "passive"))
      (node (ref "D3") (pin "2") (pinfunction "K_2") (pintype "passive"))
      (node (ref "P2") (pin "1") (pinfunction "1_1") (pintype "passive"))
      (node (ref "R4") (pin "2") (pinfunction "2_2") (pintype "passive"))
      (node (ref "U3") (pin "6") (pinfunction "A_6") (pintype "bidirectional"))
    )
    (net (code "53") (name "Net-(D4-A)") (class "Default")
      (node (ref "D4") (pin "1") (pinfunction "A_1") (pintype "passive"))
      (node (ref "D7") (pin "2") (pinfunction "K_2") (pintype "passive"))
      (node (ref "P3") (pin "2") (pinfunction "2_2") (pintype "passive"))
      (node (ref "R9") (pin "1") (pinfunction "1_1") (pintype "passive"))
      (node (ref "U6") (pin "7") (pinfunction "~{B}_7") (pintype "bidirectional"))
    )
    (net (code "54") (name "Net-(D5-PadA)") (class "Default")
      (node (ref "D5") (pin "A") (pinfunction "A_A") (pintype "passive"))
      (node (ref "R7") (pin "2") (pinfunction "2_2") (pintype "passive"))
    )
    (net (code "55") (name "Net-(D6-PadA)") (class "Default")
      (node (ref "D6") (pin "A") (pinfunction "A_A") (pintype "passive"))
      (node (ref "R8") (pin "2") (pinfunction "2_2") (pintype "passive"))
    )
    (net (code "56") (name "Net-(D7-A)") (class "Default")
      (node (ref "D7") (pin "1") (pinfunction "A_1") (pintype "passive"))
      (node (ref "D9") (pin "2") (pinfunction "K_2") (pintype "passive"))
      (node (ref "P3") (pin "1") (pinfunction "1_1") (pintype "passive"))
      (node (ref "R12") (pin "2") (pinfunction "2_2") (pintype "passive"))
      (node (ref "U6") (pin "6") (pinfunction "A_6") (pintype "bidirectional"))
    )
    (net (code "57") (name "Net-(D8-K)") (class "Default")
      (node (ref "D8") (pin "2") (pinfunction "K_2") (pintype "passive"))
      (node (ref "L1") (pin "1") (pinfunction "1_1") (pintype "passive"))
      (node (ref "U5") (pin "2") (pinfunction "OUT_2") (pintype "passive"))
    )
    (net (code "58") (name "Net-(D10-PadA)") (class "Default")
      (node (ref "D10") (pin "A") (pinfunction "A_A") (pintype "passive"))
      (node (ref "R20") (pin "2") (pinfunction "2_2") (pintype "passive"))
    )
    (net (code "59") (name "Net-(LED1-Pad2)") (class "Default")
      (node (ref "LED1") (pin "2") (pinfunction "2_2") (pintype "passive"))
      (node (ref "R14") (pin "2") (pinfunction "2_2") (pintype "passive"))
    )
    (net (code "60") (name "Net-(LED2-Pad2)") (class "Default")
      (node (ref "LED2") (pin "2") (pinfunction "2_2") (pintype "passive"))
      (node (ref "R19") (pin "2") (pinfunction "2_2") (pintype "passive"))
    )
    (net (code "61") (name "Net-(Q1-B)") (class "Default")
      (node (ref "Q1") (pin "1") (pinfunction "B_1") (pintype "passive"))
      (node (ref "R6") (pin "2") (pinfunction "2_2") (pintype "passive"))
    )
    (net (code "62") (name "Net-(Q1-C)") (class "Default")
      (node (ref "Q1") (pin "3") (pinfunction "C_3") (pintype "passive"))
      (node (ref "R3") (pin "1") (pinfunction "1_1") (pintype "passive"))
      (node (ref "U3") (pin "2") (pinfunction "~{RE}_2") (pintype "input"))
      (node (ref "U3") (pin "3") (pinfunction "DE_3") (pintype "input"))
    )
    (net (code "63") (name "Net-(Q2-B)") (class "Default")
      (node (ref "Q2") (pin "1") (pinfunction "B_1") (pintype "passive"))
      (node (ref "R13") (pin "2") (pinfunction "2_2") (pintype "passive"))
    )
    (net (code "64") (name "Net-(Q2-C)") (class "Default")
      (node (ref "Q2") (pin "3") (pinfunction "C_3") (pintype "passive"))
      (node (ref "R11") (pin "1") (pinfunction "1_1") (pintype "passive"))
      (node (ref "U6") (pin "2") (pinfunction "~{RE}_2") (pintype "input"))
      (node (ref "U6") (pin "3") (pinfunction "DE_3") (pintype "input"))
    )
    (net (code "65") (name "Net-(Q3-B)") (class "Default")
      (node (ref "Q3") (pin "1") (pinfunction "B_1") (pintype "passive"))
      (node (ref "R16") (pin "1") (pinfunction "1_1") (pintype "passive"))
      (node (ref "R18") (pin "1") (pinfunction "1_1") (pintype "passive"))
    )
    (net (code "66") (name "Net-(Q3-C)") (class "Default")
      (node (ref "Q3") (pin "3") (pinfunction "C_3") (pintype "passive"))
      (node (ref "R14") (pin "1") (pinfunction "1_1") (pintype "passive"))
    )
    (net (code "67") (name "Net-(Q4-B)") (class "Default")
      (node (ref "Q4") (pin "1") (pinfunction "B_1") (pintype "passive"))
      (node (ref "R21") (pin "1") (pinfunction "1_1") (pintype "passive"))
      (node (ref "R22") (pin "1") (pinfunction "1_1") (pintype "passive"))
    )
    (net (code "68") (name "Net-(Q4-C)") (class "Default")
      (node (ref "Q4") (pin "3") (pinfunction "C_3") (pintype "passive"))
      (node (ref "R19") (pin "1") (pinfunction "1_1") (pintype "passive"))
    )
    (net (code "69") (name "Net-(U2-OE)") (class "Default")
      (node (ref "R5") (pin "2") (pinfunction "2_2") (pintype "passive"))
      (node (ref "U2") (pin "10") (pinfunction "OE_10") (pintype "passive"))
    )
    (net (code "70") (name "Net-(U3-DI)") (class "Default")
      (node (ref "R6") (pin "1") (pinfunction "1_1") (pintype "passive"))
      (node (ref "U3") (pin "4") (pinfunction "DI_4") (pintype "input"))
    )
    (net (code "71") (name "Net-(U3-RO)") (class "Default")
      (node (ref "R2") (pin "2") (pinfunction "2_2") (pintype "passive"))
      (node (ref "U3") (pin "1") (pinfunction "RO_1") (pintype "output"))
    )
    (net (code "72") (name "Net-(U6-RO)") (class "Default")
      (node (ref "R10") (pin "2") (pinfunction "2_2") (pintype "passive"))
      (node (ref "U6") (pin "1") (pinfunction "RO_1") (pintype "output"))
    )
    (net (code "73") (name "Net-(U8-BOOT1{slash}PB2)") (class "Default")
      (node (ref "R24") (pin "1") (pinfunction "1_1") (pintype "passive"))
      (node (ref "U8") (pin "20") (pinfunction "BOOT1/PB2_20") (pintype "bidirectional"))
    )
    (net (code "74") (name "VCC_1.8V") (class "Default")
      (node (ref "C2") (pin "1") (pinfunction "1_1") (pintype "passive"))
      (node (ref "P1") (pin "4") (pinfunction "4_4") (pintype "passive"))
      (node (ref "R5") (pin "1") (pinfunction "1_1") (pintype "passive"))
      (node (ref "U2") (pin "2") (pinfunction "VCCA_2") (pintype "passive"))
    )
    (net (code "75") (name "VCC_3.3V") (class "Default")
      (node (ref "C12") (pin "2") (pinfunction "2_2") (pintype "passive"))
      (node (ref "C13") (pin "2") (pinfunction "2_2") (pintype "passive"))
      (node (ref "C15") (pin "2") (pinfunction "2_2") (pintype "passive"))
      (node (ref "C19") (pin "2") (pinfunction "2_2") (pintype "passive"))
      (node (ref "C20") (pin "2") (pinfunction "2_2") (pintype "passive"))
      (node (ref "C21") (pin "2") (pinfunction "2_2") (pintype "passive"))
      (node (ref "C22") (pin "2") (pinfunction "2_2") (pintype "passive"))
      (node (ref "C3") (pin "1") (pinfunction "1_1") (pintype "passive"))
      (node (ref "C8") (pin "2") (pinfunction "2_2") (pintype "passive"))
      (node (ref "C9") (pin "2") (pinfunction "2_2") (pintype "passive"))
      (node (ref "E2") (pin "1") (pinfunction "1_1") (pintype "passive"))
      (node (ref "P1") (pin "37") (pinfunction "37_37") (pintype "passive"))
      (node (ref "P10") (pin "1") (pinfunction "1_1") (pintype "passive"))
      (node (ref "P7") (pin "2") (pinfunction "2_2") (pintype "passive"))
      (node (ref "R15") (pin "2") (pinfunction "2_2") (pintype "passive"))
      (node (ref "R17") (pin "1") (pinfunction "1_1") (pintype "passive"))
      (node (ref "R23") (pin "2") (pinfunction "2_2") (pintype "passive"))
      (node (ref "R7") (pin "1") (pinfunction "1_1") (pintype "passive"))
      (node (ref "R8") (pin "1") (pinfunction "1_1") (pintype "passive"))
      (node (ref "U2") (pin "19") (pinfunction "VCCB_19") (pintype "passive"))
      (node (ref "U8") (pin "1") (pinfunction "VBAT_1") (pintype "power_in"))
      (node (ref "U8") (pin "24") (pinfunction "VDD_1_24") (pintype "power_in"))
      (node (ref "U8") (pin "36") (pinfunction "VDD_2_36") (pintype "power_in"))
      (node (ref "U8") (pin "48") (pinfunction "VDD_3_48") (pintype "power_in"))
      (node (ref "U8") (pin "9") (pinfunction "VDDA_9") (pintype "power_in"))
      (node (ref "VR1") (pin "2") (pinfunction "Vout_2") (pintype "passive"))
      (node (ref "VR2") (pin "2") (pinfunction "Vout_2") (pintype "passive"))
      (node (ref "u7") (pin "3") (pinfunction "3V3_3") (pintype "passive"))
    )
    (net (code "76") (name "VCC_5V") (class "Default")
      (node (ref "C10") (pin "2") (pinfunction "2_2") (pintype "passive"))
      (node (ref "C11") (pin "2") (pinfunction "2_2") (pintype "passive"))
      (node (ref "C14") (pin "2") (pinfunction "2_2") (pintype "passive"))
      (node (ref "C4") (pin "2") (pinfunction "2_2") (pintype "passive"))
      (node (ref "C6") (pin "2") (pinfunction "2_2") (pintype "passive"))
      (node (ref "C7") (pin "2") (pinfunction "2_2") (pintype "passive"))
      (node (ref "E1") (pin "1") (pinfunction "1_1") (pintype "passive"))
      (node (ref "L1") (pin "2") (pinfunction "2_2") (pintype "passive"))
      (node (ref "LED1") (pin "1") (pinfunction "1_1") (pintype "passive"))
      (node (ref "LED2") (pin "1") (pinfunction "1_1") (pintype "passive"))
      (node (ref "P1") (pin "3") (pinfunction "3_3") (pintype "passive"))
      (node (ref "R11") (pin "2") (pinfunction "2_2") (pintype "passive"))
      (node (ref "R12") (pin "1") (pinfunction "1_1") (pintype "passive"))
      (node (ref "R3") (pin "2") (pinfunction "2_2") (pintype "passive"))
      (node (ref "R4") (pin "1") (pinfunction "1_1") (pintype "passive"))
      (node (ref "U3") (pin "8") (pinfunction "VCC_8") (pintype "power_in"))
      (node (ref "U5") (pin "4") (pinfunction "Feedback_4") (pintype "input"))
      (node (ref "U6") (pin "8") (pinfunction "VCC_8") (pintype "power_in"))
      (node (ref "VR1") (pin "3") (pinfunction "Vin_3") (pintype "passive"))
      (node (ref "VR2") (pin "3") (pinfunction "Vin_3") (pintype "passive"))
    )
    (net (code "77") (name "VCC_24V") (class "Default")
      (node (ref "C5") (pin "2") (pinfunction "2_2") (pintype "passive"))
      (node (ref "P5") (pin "1") (pinfunction "1_1") (pintype "passive"))
      (node (ref "P6") (pin "1") (pinfunction "1_1") (pintype "passive"))
      (node (ref "U5") (pin "1") (pinfunction "VIN_1") (pintype "passive"))
    )
    (net (code "78") (name "unconnected-(P1-Pad8)") (class "Default")
      (node (ref "P1") (pin "8") (pinfunction "8_8") (pintype "passive"))
    )
    (net (code "79") (name "unconnected-(P1-Pad10)") (class "Default")
      (node (ref "P1") (pin "10") (pinfunction "10_10") (pintype "passive"))
    )
    (net (code "80") (name "unconnected-(P1-Pad12)") (class "Default")
      (node (ref "P1") (pin "12") (pinfunction "12_12") (pintype "passive"))
    )
    (net (code "81") (name "unconnected-(P1-Pad14)") (class "Default")
      (node (ref "P1") (pin "14") (pinfunction "14_14") (pintype "passive"))
    )
    (net (code "82") (name "unconnected-(P1-Pad15)") (class "Default")
      (node (ref "P1") (pin "15") (pinfunction "15_15") (pintype "passive"))
    )
    (net (code "83") (name "unconnected-(P1-Pad16)") (class "Default")
      (node (ref "P1") (pin "16") (pinfunction "16_16") (pintype "passive"))
    )
    (net (code "84") (name "unconnected-(P1-Pad17)") (class "Default")
      (node (ref "P1") (pin "17") (pinfunction "17_17") (pintype "passive"))
    )
    (net (code "85") (name "unconnected-(P1-Pad18)") (class "Default")
      (node (ref "P1") (pin "18") (pinfunction "18_18") (pintype "passive"))
    )
    (net (code "86") (name "unconnected-(P1-Pad20)") (class "Default")
      (node (ref "P1") (pin "20") (pinfunction "20_20") (pintype "passive"))
    )
    (net (code "87") (name "unconnected-(P1-Pad22)") (class "Default")
      (node (ref "P1") (pin "22") (pinfunction "22_22") (pintype "passive"))
    )
    (net (code "88") (name "unconnected-(P1-Pad27)") (class "Default")
      (node (ref "P1") (pin "27") (pinfunction "27_27") (pintype "passive"))
    )
    (net (code "89") (name "unconnected-(P1-Pad29)") (class "Default")
      (node (ref "P1") (pin "29") (pinfunction "29_29") (pintype "passive"))
    )
    (net (code "90") (name "unconnected-(P1-Pad31)") (class "Default")
      (node (ref "P1") (pin "31") (pinfunction "31_31") (pintype "passive"))
    )
    (net (code "91") (name "unconnected-(P1-Pad32)") (class "Default")
      (node (ref "P1") (pin "32") (pinfunction "32_32") (pintype "passive"))
    )
    (net (code "92") (name "unconnected-(P1-Pad34)") (class "Default")
      (node (ref "P1") (pin "34") (pinfunction "34_34") (pintype "passive"))
    )
    (net (code "93") (name "unconnected-(P1-Pad36)") (class "Default")
      (node (ref "P1") (pin "36") (pinfunction "36_36") (pintype "passive"))
    )
    (net (code "94") (name "unconnected-(U1-VPP-Pad5)") (class "Default")
      (node (ref "U1") (pin "5") (pinfunction "VPP_5") (pintype "passive"))
    )
    (net (code "95") (name "unconnected-(U4-Pad4)") (class "Default")
      (node (ref "U4") (pin "4") (pinfunction "4_4") (pintype "passive"))
    )
    (net (code "96") (name "unconnected-(U8-PA0{slash}WKUP{slash}USART2_CTS{slash}ADC12_IN0{slash}TIM2_CH1_ETR-Pad10)") (class "Default")
      (node (ref "U8") (pin "10") (pinfunction "PA0/WKUP/USART2_CTS/ADC12_IN0/TIM2_CH1_ETR_10") (pintype "bidirectional"))
    )
    (net (code "97") (name "unconnected-(U8-PA1{slash}USART2_RTS{slash}ADC12_IN1{slash}TIM2_CH2-Pad11)") (class "Default")
      (node (ref "U8") (pin "11") (pinfunction "PA1/USART2_RTS/ADC12_IN1/TIM2_CH2_11") (pintype "bidirectional"))
    )
    (net (code "98") (name "unconnected-(U8-PA7{slash}SPI1_MOSI{slash}ADC12_IN7{slash}TIM3_CH2-Pad17)") (class "Default")
      (node (ref "U8") (pin "17") (pinfunction "PA7/SPI1_MOSI/ADC12_IN7/TIM3_CH2_17") (pintype "bidirectional"))
    )
    (net (code "99") (name "unconnected-(U8-PA8{slash}USART1_CK{slash}TIM1_CH1{slash}MCO-Pad29)") (class "Default")
      (node (ref "U8") (pin "29") (pinfunction "PA8/USART1_CK/TIM1_CH1/MCO_29") (pintype "bidirectional"))
    )
    (net (code "100") (name "unconnected-(U8-PA11{slash}USART1_CTS{slash}CANRX{slash}TIM1_CH4{slash}USBDM-Pad32)") (class "Default")
      (node (ref "U8") (pin "32") (pinfunction "PA11/USART1_CTS/CANRX/TIM1_CH4/USBDM_32") (pintype "bidirectional"))
    )
    (net (code "101") (name "unconnected-(U8-PA12{slash}USART1_RTS{slash}CANTX{slash}TIM1_ETR{slash}USBDP-Pad33)") (class "Default")
      (node (ref "U8") (pin "33") (pinfunction "PA12/USART1_RTS/CANTX/TIM1_ETR/USBDP_33") (pintype "bidirectional"))
    )
    (net (code "102") (name "unconnected-(U8-PA15{slash}JTDI-Pad38)") (class "Default")
      (node (ref "U8") (pin "38") (pinfunction "PA15/JTDI_38") (pintype "bidirectional"))
    )
    (net (code "103") (name "unconnected-(U8-PC13-TAMPER-RTC-Pad2)") (class "Default")
      (node (ref "U8") (pin "2") (pinfunction "PC13-TAMPER-RTC_2") (pintype "bidirectional"))
    )
    (net (code "104") (name "unconnected-(U8-TIM1_BKIN{slash}USART3_CK{slash}I2C2_SMBAL{slash}SPI2_NSS{slash}PB12-Pad25)") (class "Default")
      (node (ref "U8") (pin "25") (pinfunction "TIM1_BKIN/USART3_CK/I2C2_SMBAL/SPI2_NSS/PB12_25") (pintype "bidirectional"))
    )
    (net (code "105") (name "unconnected-(U8-TIM1_CH1N{slash}USART3_CTS{slash}SPI2_SCK{slash}PB13-Pad26)") (class "Default")
      (node (ref "U8") (pin "26") (pinfunction "TIM1_CH1N/USART3_CTS/SPI2_SCK/PB13_26") (pintype "bidirectional"))
    )
    (net (code "106") (name "unconnected-(U8-TIM1_CH2N{slash}USART3_RTS{slash}SPI2_MISO{slash}PB14-Pad27)") (class "Default")
      (node (ref "U8") (pin "27") (pinfunction "TIM1_CH2N/USART3_RTS/SPI2_MISO/PB14_27") (pintype "bidirectional"))
    )
    (net (code "107") (name "unconnected-(U8-TIM1_CH3N{slash}SPI2_MOSI{slash}PB15-Pad28)") (class "Default")
      (node (ref "U8") (pin "28") (pinfunction "TIM1_CH3N/SPI2_MOSI/PB15_28") (pintype "bidirectional"))
    )
    (net (code "108") (name "unconnected-(U8-TIM4_CH4{slash}PB9-Pad46)") (class "Default")
      (node (ref "U8") (pin "46") (pinfunction "TIM4_CH4/PB9_46") (pintype "bidirectional"))
    )
    (net (code "109") (name "unconnected-(u7-ANT-Pad1)") (class "Default")
      (node (ref "u7") (pin "1") (pinfunction "ANT_1") (pintype "passive"))
    )
    (net (code "110") (name "unconnected-(u7-DIO1-Pad6)") (class "Default")
      (node (ref "u7") (pin "6") (pinfunction "DIO1_6") (pintype "passive"))
    )
    (net (code "111") (name "unconnected-(u7-DIO2-Pad7)") (class "Default")
      (node (ref "u7") (pin "7") (pinfunction "DIO2_7") (pintype "passive"))
    )
    (net (code "112") (name "unconnected-(u7-DIO3-Pad8)") (class "Default")
      (node (ref "u7") (pin "8") (pinfunction "DIO3_8") (pintype "passive"))
    )
    (net (code "113") (name "unconnected-(u7-DIO4-Pad10)") (class "Default")
      (node (ref "u7") (pin "10") (pinfunction "DIO4_10") (pintype "passive"))
    )
    (net (code "114") (name "unconnected-(u7-DIO5-Pad11)") (class "Default")
      (node (ref "u7") (pin "11") (pinfunction "DIO5_11") (pintype "passive"))
    )
  )
)
